# ASD2113.net
KiCad netlist of a schematic drawn in EAGLE
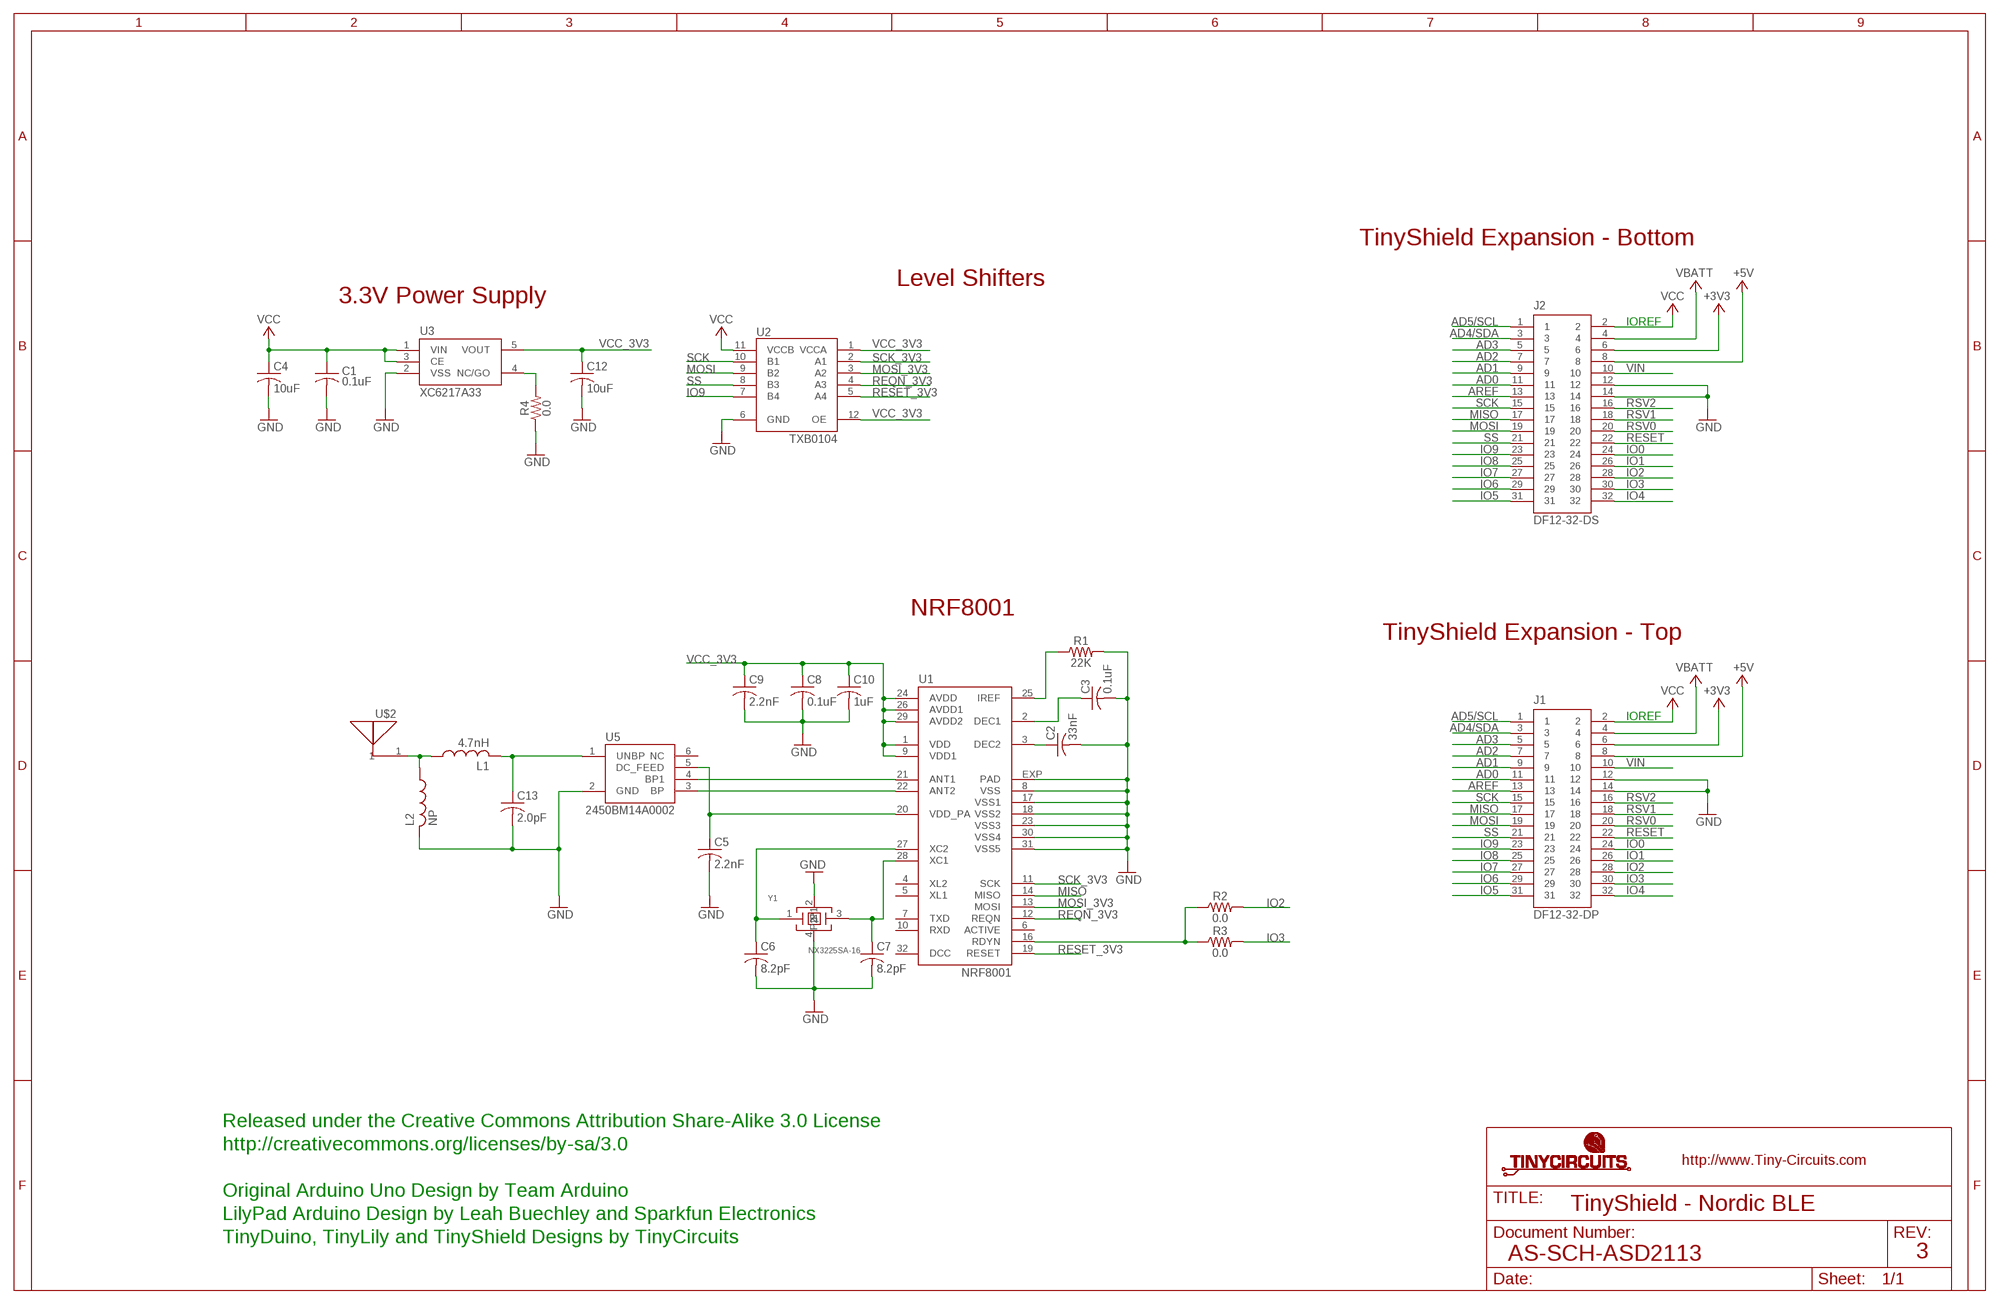
[diagram p0: schematic, sheet 1]

(export (version "E")
  (design (tool "Eeschema 10.0.6"))
  (components
    (comp (ref "C1")
      (value "0.1uF")
      (footprint "eagle-import:C0402")
      (fields (field (name "PARTNO") "AS-ITM-00008") (field (name "PARTNO_1") "AS-ITM-00008"))
      (libsource (lib "eagle-import") (part "AS-ITM-00008"))
    )
    (comp (ref "C2")
      (value "33nF")
      (footprint "eagle-import:C0402")
      (fields (field (name "PARTNO") "AS-ITM-00248") (field (name "PARTNO_1") "AS-ITM-00248"))
      (libsource (lib "eagle-import") (part "AS-ITM-00248"))
    )
    (comp (ref "C3")
      (value "0.1uF")
      (footprint "eagle-import:C0402")
      (fields (field (name "PARTNO") "AS-ITM-00008"))
      (libsource (lib "eagle-import") (part "AS-ITM-00008"))
    )
    (comp (ref "C4")
      (value "10uF")
      (footprint "eagle-import:C0805")
      (fields (field (name "PARTNO") "AS-ITM-00045") (field (name "PARTNO_1") "AS-ITM-00045"))
      (libsource (lib "eagle-import") (part "AS-ITM-00045"))
    )
    (comp (ref "C5")
      (value "2.2nF")
      (footprint "eagle-import:C0402")
      (fields (field (name "PARTNO") "AS-ITM-00085"))
      (libsource (lib "eagle-import") (part "AS-ITM-00085"))
    )
    (comp (ref "C6")
      (value "8.2pF")
      (footprint "eagle-import:C0402")
      (fields (field (name "PARTNO") "AS-ITM-00247") (field (name "PARTNO_1") "AS-ITM-00247"))
      (libsource (lib "eagle-import") (part "AS-ITM-00247"))
    )
    (comp (ref "C7")
      (value "8.2pF")
      (footprint "eagle-import:C0402")
      (fields (field (name "PARTNO") "AS-ITM-00247") (field (name "PARTNO_1") "AS-ITM-00247"))
      (libsource (lib "eagle-import") (part "AS-ITM-00247"))
    )
    (comp (ref "C8")
      (value "0.1uF")
      (footprint "eagle-import:C0402")
      (fields (field (name "PARTNO") "AS-ITM-00008"))
      (libsource (lib "eagle-import") (part "AS-ITM-00008"))
    )
    (comp (ref "C9")
      (value "2.2nF")
      (footprint "eagle-import:C0402")
      (fields (field (name "PARTNO") "AS-ITM-00085"))
      (libsource (lib "eagle-import") (part "AS-ITM-00085"))
    )
    (comp (ref "C10")
      (value "1uF")
      (footprint "eagle-import:C0402")
      (fields (field (name "PARTNO") "AS-ITM-00105"))
      (libsource (lib "eagle-import") (part "AS-ITM-00105"))
    )
    (comp (ref "C12")
      (value "10uF")
      (footprint "eagle-import:C0805")
      (fields (field (name "PARTNO") "AS-ITM-00045") (field (name "PARTNO_1") "AS-ITM-00045"))
      (libsource (lib "eagle-import") (part "AS-ITM-00045"))
    )
    (comp (ref "C13")
      (value "2.0pF")
      (footprint "eagle-import:C0402")
      (fields (field (name "PARTNO") "AS-ITM-00245") (field (name "PARTNO_1") "AS-ITM-00245"))
      (libsource (lib "eagle-import") (part "AS-ITM-00245"))
    )
    (comp (ref "J1")
      (value "DF12-32-DP")
      (footprint "eagle-import:DF12-32-DP")
      (fields (field (name "PARTNO") "AS-ITM-00015") (field (name "PARTNO_1") "AS-ITM-00015"))
      (libsource (lib "eagle-import") (part "AS-ITM-00015"))
    )
    (comp (ref "J2")
      (value "DF12-32-DS")
      (footprint "eagle-import:DF12-32-DS")
      (fields (field (name "PARTNO") "AS-ITM-00012") (field (name "PARTNO_1") "AS-ITM-00012"))
      (libsource (lib "eagle-import") (part "AS-ITM-00012"))
    )
    (comp (ref "L1")
      (value "4.7nH")
      (footprint "eagle-import:C0402")
      (fields (field (name "PARTNO") "AS-ITM-00246") (field (name "PARTNO_1") "AS-ITM-00246"))
      (libsource (lib "eagle-import") (part "AS-ITM-00246"))
    )
    (comp (ref "L2")
      (value "NP")
      (footprint "eagle-import:C0402")
      (fields (field (name "PARTNO") "AS-ITM-00108"))
      (libsource (lib "eagle-import") (part "AS-ITM-00108"))
    )
    (comp (ref "R1")
      (value "22K")
      (footprint "eagle-import:0402")
      (fields (field (name "PARTNO") "AS-ITM-00147"))
      (libsource (lib "eagle-import") (part "AS-ITM-00147"))
    )
    (comp (ref "R2")
      (value "0.0")
      (footprint "eagle-import:0402")
      (fields (field (name "PARTNO") "AS-ITM-00076") (field (name "PARTNO_1") "AS-ITM-00076"))
      (libsource (lib "eagle-import") (part "AS-ITM-00076"))
    )
    (comp (ref "R3")
      (value "0.0")
      (footprint "eagle-import:0402")
      (fields (field (name "PARTNO") "AS-ITM-00076") (field (name "PARTNO_1") "AS-ITM-00076"))
      (libsource (lib "eagle-import") (part "AS-ITM-00076"))
    )
    (comp (ref "R4")
      (value "0.0")
      (footprint "eagle-import:0402")
      (fields (field (name "PARTNO") "AS-ITM-00076"))
      (libsource (lib "eagle-import") (part "AS-ITM-00076"))
    )
    (comp (ref "U$2")
      (value "AS-ITM-00132")
      (footprint "eagle-import:2450AT18A100")
      (fields (field (name "PARTNO") "AS-ITM-00132"))
      (libsource (lib "eagle-import") (part "AS-ITM-00132"))
    )
    (comp (ref "U1")
      (value "NRF8001")
      (footprint "eagle-import:ATMEL_QFN32")
      (fields (field (name "PARTNO") "AS-ITM-00227"))
      (libsource (lib "eagle-import") (part "AS-ITM-00227"))
    )
    (comp (ref "U2")
      (value "TXB0104")
      (footprint "eagle-import:UQFN-12")
      (fields (field (name "PARTNO") "AS-ITM-00048"))
      (libsource (lib "eagle-import") (part "AS-ITM-00048"))
    )
    (comp (ref "U3")
      (value "XC6217A33")
      (footprint "eagle-import:SOT-25")
      (fields (field (name "PARTNO") "AS-ITM-00249") (field (name "PARTNO_1") "AS-ITM-00249"))
      (libsource (lib "eagle-import") (part "AS-ITM-00249"))
    )
    (comp (ref "U5")
      (value "2450BM14A0002")
      (footprint "eagle-import:2450BM14A0002")
      (fields (field (name "PARTNO") "AS-ITM-00114"))
      (libsource (lib "eagle-import") (part "AS-ITM-00114"))
    )
    (comp (ref "Y1")
      (value "NX3225SA-16")
      (footprint "eagle-import:ABM11")
      (fields (field (name "PARTNO") "AS-ITM-00228") (field (name "PARTNO_1") "AS-ITM-00228"))
      (libsource (lib "eagle-import") (part "AS-ITM-00228"))
    )
  )
  (nets
    (net (code "1") (name "+3V3") (class "Default")
      (node (ref "J1") (pin "6") (pinfunction "6_6") (pintype "bidirectional"))
      (node (ref "J2") (pin "6") (pinfunction "6_6") (pintype "bidirectional"))
    )
    (net (code "2") (name "+5V") (class "Default")
      (node (ref "J1") (pin "8") (pinfunction "8_8") (pintype "bidirectional"))
      (node (ref "J2") (pin "8") (pinfunction "8_8") (pintype "bidirectional"))
    )
    (net (code "3") (name "/AD0") (class "Default")
      (node (ref "J1") (pin "11") (pinfunction "11_11") (pintype "bidirectional"))
      (node (ref "J2") (pin "11") (pinfunction "11_11") (pintype "bidirectional"))
    )
    (net (code "4") (name "/AD1") (class "Default")
      (node (ref "J1") (pin "9") (pinfunction "9_9") (pintype "bidirectional"))
      (node (ref "J2") (pin "9") (pinfunction "9_9") (pintype "bidirectional"))
    )
    (net (code "5") (name "/AD2") (class "Default")
      (node (ref "J1") (pin "7") (pinfunction "7_7") (pintype "bidirectional"))
      (node (ref "J2") (pin "7") (pinfunction "7_7") (pintype "bidirectional"))
    )
    (net (code "6") (name "/AD3") (class "Default")
      (node (ref "J1") (pin "5") (pinfunction "5_5") (pintype "bidirectional"))
      (node (ref "J2") (pin "5") (pinfunction "5_5") (pintype "bidirectional"))
    )
    (net (code "7") (name "/AD4{slash}SDA") (class "Default")
      (node (ref "J1") (pin "3") (pinfunction "3_3") (pintype "bidirectional"))
      (node (ref "J2") (pin "3") (pinfunction "3_3") (pintype "bidirectional"))
    )
    (net (code "8") (name "/AD5{slash}SCL") (class "Default")
      (node (ref "J1") (pin "1") (pinfunction "1_1") (pintype "bidirectional"))
      (node (ref "J2") (pin "1") (pinfunction "1_1") (pintype "bidirectional"))
    )
    (net (code "9") (name "/AREF") (class "Default")
      (node (ref "J1") (pin "13") (pinfunction "13_13") (pintype "bidirectional"))
      (node (ref "J2") (pin "13") (pinfunction "13_13") (pintype "bidirectional"))
    )
    (net (code "10") (name "/IO0") (class "Default")
      (node (ref "J1") (pin "24") (pinfunction "24_24") (pintype "bidirectional"))
      (node (ref "J2") (pin "24") (pinfunction "24_24") (pintype "bidirectional"))
    )
    (net (code "11") (name "/IO1") (class "Default")
      (node (ref "J1") (pin "26") (pinfunction "26_26") (pintype "bidirectional"))
      (node (ref "J2") (pin "26") (pinfunction "26_26") (pintype "bidirectional"))
    )
    (net (code "12") (name "/IO2") (class "Default")
      (node (ref "J1") (pin "28") (pinfunction "28_28") (pintype "bidirectional"))
      (node (ref "J2") (pin "28") (pinfunction "28_28") (pintype "bidirectional"))
      (node (ref "R2") (pin "2") (pinfunction "2_2") (pintype "passive"))
    )
    (net (code "13") (name "/IO3") (class "Default")
      (node (ref "J1") (pin "30") (pinfunction "30_30") (pintype "bidirectional"))
      (node (ref "J2") (pin "30") (pinfunction "30_30") (pintype "bidirectional"))
      (node (ref "R3") (pin "2") (pinfunction "2_2") (pintype "passive"))
    )
    (net (code "14") (name "/IO4") (class "Default")
      (node (ref "J1") (pin "32") (pinfunction "32_32") (pintype "bidirectional"))
      (node (ref "J2") (pin "32") (pinfunction "32_32") (pintype "bidirectional"))
    )
    (net (code "15") (name "/IO5") (class "Default")
      (node (ref "J1") (pin "31") (pinfunction "31_31") (pintype "bidirectional"))
      (node (ref "J2") (pin "31") (pinfunction "31_31") (pintype "bidirectional"))
    )
    (net (code "16") (name "/IO6") (class "Default")
      (node (ref "J1") (pin "29") (pinfunction "29_29") (pintype "bidirectional"))
      (node (ref "J2") (pin "29") (pinfunction "29_29") (pintype "bidirectional"))
    )
    (net (code "17") (name "/IO7") (class "Default")
      (node (ref "J1") (pin "27") (pinfunction "27_27") (pintype "bidirectional"))
      (node (ref "J2") (pin "27") (pinfunction "27_27") (pintype "bidirectional"))
    )
    (net (code "18") (name "/IO8") (class "Default")
      (node (ref "J1") (pin "25") (pinfunction "25_25") (pintype "bidirectional"))
      (node (ref "J2") (pin "25") (pinfunction "25_25") (pintype "bidirectional"))
    )
    (net (code "19") (name "/IO9") (class "Default")
      (node (ref "J1") (pin "23") (pinfunction "23_23") (pintype "bidirectional"))
      (node (ref "J2") (pin "23") (pinfunction "23_23") (pintype "bidirectional"))
      (node (ref "U2") (pin "7") (pinfunction "B4_7") (pintype "bidirectional"))
    )
    (net (code "20") (name "/MISO") (class "Default")
      (node (ref "J1") (pin "17") (pinfunction "17_17") (pintype "bidirectional"))
      (node (ref "J2") (pin "17") (pinfunction "17_17") (pintype "bidirectional"))
      (node (ref "U1") (pin "14") (pinfunction "MISO_14") (pintype "bidirectional"))
    )
    (net (code "21") (name "/MOSI") (class "Default")
      (node (ref "J1") (pin "19") (pinfunction "19_19") (pintype "bidirectional"))
      (node (ref "J2") (pin "19") (pinfunction "19_19") (pintype "bidirectional"))
      (node (ref "U2") (pin "9") (pinfunction "B2_9") (pintype "bidirectional"))
    )
    (net (code "22") (name "/MOSI_3V3") (class "Default")
      (node (ref "U1") (pin "13") (pinfunction "MOSI_13") (pintype "bidirectional"))
      (node (ref "U2") (pin "3") (pinfunction "A2_3") (pintype "bidirectional"))
    )
    (net (code "23") (name "/REQN_3V3") (class "Default")
      (node (ref "U1") (pin "12") (pinfunction "REQN_12") (pintype "bidirectional"))
      (node (ref "U2") (pin "4") (pinfunction "A3_4") (pintype "bidirectional"))
    )
    (net (code "24") (name "/RESET") (class "Default")
      (node (ref "J1") (pin "22") (pinfunction "22_22") (pintype "bidirectional"))
      (node (ref "J2") (pin "22") (pinfunction "22_22") (pintype "bidirectional"))
    )
    (net (code "25") (name "/RESET_3V3") (class "Default")
      (node (ref "U1") (pin "19") (pinfunction "RESET_19") (pintype "bidirectional"))
      (node (ref "U2") (pin "5") (pinfunction "A4_5") (pintype "bidirectional"))
    )
    (net (code "26") (name "/RSV0") (class "Default")
      (node (ref "J1") (pin "20") (pinfunction "20_20") (pintype "bidirectional"))
      (node (ref "J2") (pin "20") (pinfunction "20_20") (pintype "bidirectional"))
    )
    (net (code "27") (name "/RSV1") (class "Default")
      (node (ref "J1") (pin "18") (pinfunction "18_18") (pintype "bidirectional"))
      (node (ref "J2") (pin "18") (pinfunction "18_18") (pintype "bidirectional"))
    )
    (net (code "28") (name "/RSV2") (class "Default")
      (node (ref "J1") (pin "16") (pinfunction "16_16") (pintype "bidirectional"))
      (node (ref "J2") (pin "16") (pinfunction "16_16") (pintype "bidirectional"))
    )
    (net (code "29") (name "/SCK") (class "Default")
      (node (ref "J1") (pin "15") (pinfunction "15_15") (pintype "bidirectional"))
      (node (ref "J2") (pin "15") (pinfunction "15_15") (pintype "bidirectional"))
      (node (ref "U2") (pin "10") (pinfunction "B1_10") (pintype "bidirectional"))
    )
    (net (code "30") (name "/SCK_3V3") (class "Default")
      (node (ref "U1") (pin "11") (pinfunction "SCK_11") (pintype "bidirectional"))
      (node (ref "U2") (pin "2") (pinfunction "A1_2") (pintype "bidirectional"))
    )
    (net (code "31") (name "/SS") (class "Default")
      (node (ref "J1") (pin "21") (pinfunction "21_21") (pintype "bidirectional"))
      (node (ref "J2") (pin "21") (pinfunction "21_21") (pintype "bidirectional"))
      (node (ref "U2") (pin "8") (pinfunction "B3_8") (pintype "bidirectional"))
    )
    (net (code "32") (name "/VCC_3V3") (class "Default")
      (node (ref "C10") (pin "1") (pinfunction "1_1") (pintype "passive"))
      (node (ref "C12") (pin "1") (pinfunction "1_1") (pintype "passive"))
      (node (ref "C8") (pin "1") (pinfunction "1_1") (pintype "passive"))
      (node (ref "C9") (pin "1") (pinfunction "1_1") (pintype "passive"))
      (node (ref "U1") (pin "1") (pinfunction "VDD_1") (pintype "bidirectional"))
      (node (ref "U1") (pin "24") (pinfunction "AVDD_24") (pintype "bidirectional"))
      (node (ref "U1") (pin "26") (pinfunction "AVDD1_26") (pintype "bidirectional"))
      (node (ref "U1") (pin "29") (pinfunction "AVDD2_29") (pintype "bidirectional"))
      (node (ref "U1") (pin "9") (pinfunction "VDD1_9") (pintype "bidirectional"))
      (node (ref "U2") (pin "1") (pinfunction "VCCA_1") (pintype "bidirectional"))
      (node (ref "U2") (pin "12") (pinfunction "OE_12") (pintype "bidirectional"))
      (node (ref "U3") (pin "5") (pinfunction "VOUT_5") (pintype "bidirectional"))
    )
    (net (code "33") (name "/VIN") (class "Default")
      (node (ref "J1") (pin "10") (pinfunction "10_10") (pintype "bidirectional"))
      (node (ref "J2") (pin "10") (pinfunction "10_10") (pintype "bidirectional"))
    )
    (net (code "34") (name "GND") (class "Default")
      (node (ref "C1") (pin "2") (pinfunction "2_2") (pintype "passive"))
      (node (ref "C10") (pin "2") (pinfunction "2_2") (pintype "passive"))
      (node (ref "C12") (pin "2") (pinfunction "2_2") (pintype "passive"))
      (node (ref "C13") (pin "2") (pinfunction "2_2") (pintype "passive"))
      (node (ref "C2") (pin "2") (pinfunction "2_2") (pintype "passive"))
      (node (ref "C3") (pin "2") (pinfunction "2_2") (pintype "passive"))
      (node (ref "C4") (pin "2") (pinfunction "2_2") (pintype "passive"))
      (node (ref "C5") (pin "2") (pinfunction "2_2") (pintype "passive"))
      (node (ref "C6") (pin "2") (pinfunction "2_2") (pintype "passive"))
      (node (ref "C7") (pin "2") (pinfunction "2_2") (pintype "passive"))
      (node (ref "C8") (pin "2") (pinfunction "2_2") (pintype "passive"))
      (node (ref "C9") (pin "2") (pinfunction "2_2") (pintype "passive"))
      (node (ref "J1") (pin "12") (pinfunction "12_12") (pintype "bidirectional"))
      (node (ref "J1") (pin "14") (pinfunction "14_14") (pintype "bidirectional"))
      (node (ref "J2") (pin "12") (pinfunction "12_12") (pintype "bidirectional"))
      (node (ref "J2") (pin "14") (pinfunction "14_14") (pintype "bidirectional"))
      (node (ref "L2") (pin "2") (pinfunction "2_2") (pintype "passive"))
      (node (ref "R1") (pin "2") (pinfunction "2_2") (pintype "passive"))
      (node (ref "R4") (pin "1") (pinfunction "1_1") (pintype "passive"))
      (node (ref "U1") (pin "17") (pinfunction "VSS1_17") (pintype "bidirectional"))
      (node (ref "U1") (pin "18") (pinfunction "VSS2_18") (pintype "bidirectional"))
      (node (ref "U1") (pin "23") (pinfunction "VSS3_23") (pintype "bidirectional"))
      (node (ref "U1") (pin "30") (pinfunction "VSS4_30") (pintype "bidirectional"))
      (node (ref "U1") (pin "31") (pinfunction "VSS5_31") (pintype "bidirectional"))
      (node (ref "U1") (pin "8") (pinfunction "VSS_8") (pintype "bidirectional"))
      (node (ref "U1") (pin "EXP") (pinfunction "PAD_EXP") (pintype "bidirectional"))
      (node (ref "U2") (pin "6") (pinfunction "GND_6") (pintype "bidirectional"))
      (node (ref "U3") (pin "2") (pinfunction "VSS_2") (pintype "power_in"))
      (node (ref "U5") (pin "2") (pinfunction "GND_2") (pintype "bidirectional"))
      (node (ref "Y1") (pin "2") (pinfunction "P2_2") (pintype "bidirectional"))
      (node (ref "Y1") (pin "4") (pinfunction "P1_4") (pintype "bidirectional"))
    )
    (net (code "35") (name "Net-(L1-Pad1)") (class "Default")
      (node (ref "L1") (pin "1") (pinfunction "1_1") (pintype "passive"))
      (node (ref "L2") (pin "1") (pinfunction "1_1") (pintype "passive"))
      (node (ref "U$2") (pin "1") (pinfunction "1_1") (pintype "bidirectional"))
    )
    (net (code "36") (name "Net-(U1-ANT1)") (class "Default")
      (node (ref "U1") (pin "21") (pinfunction "ANT1_21") (pintype "bidirectional"))
      (node (ref "U5") (pin "4") (pinfunction "BP1_4") (pintype "bidirectional"))
    )
    (net (code "37") (name "Net-(U1-ANT2)") (class "Default")
      (node (ref "U1") (pin "22") (pinfunction "ANT2_22") (pintype "bidirectional"))
      (node (ref "U5") (pin "3") (pinfunction "BP_3") (pintype "bidirectional"))
    )
    (net (code "38") (name "Net-(U1-DEC1)") (class "Default")
      (node (ref "C3") (pin "1") (pinfunction "1_1") (pintype "passive"))
      (node (ref "U1") (pin "2") (pinfunction "DEC1_2") (pintype "bidirectional"))
    )
    (net (code "39") (name "Net-(U1-DEC2)") (class "Default")
      (node (ref "C2") (pin "1") (pinfunction "1_1") (pintype "passive"))
      (node (ref "U1") (pin "3") (pinfunction "DEC2_3") (pintype "bidirectional"))
    )
    (net (code "40") (name "Net-(U1-IREF)") (class "Default")
      (node (ref "R1") (pin "1") (pinfunction "1_1") (pintype "passive"))
      (node (ref "U1") (pin "25") (pinfunction "IREF_25") (pintype "bidirectional"))
    )
    (net (code "41") (name "Net-(U1-RDYN)") (class "Default")
      (node (ref "R2") (pin "1") (pinfunction "1_1") (pintype "passive"))
      (node (ref "R3") (pin "1") (pinfunction "1_1") (pintype "passive"))
      (node (ref "U1") (pin "16") (pinfunction "RDYN_16") (pintype "bidirectional"))
    )
    (net (code "42") (name "Net-(U1-VDD_PA)") (class "Default")
      (node (ref "C5") (pin "1") (pinfunction "1_1") (pintype "passive"))
      (node (ref "U1") (pin "20") (pinfunction "VDD_PA_20") (pintype "bidirectional"))
      (node (ref "U5") (pin "5") (pinfunction "DC_FEED_5") (pintype "bidirectional"))
    )
    (net (code "43") (name "Net-(U1-XC1)") (class "Default")
      (node (ref "C7") (pin "1") (pinfunction "1_1") (pintype "passive"))
      (node (ref "U1") (pin "28") (pinfunction "XC1_28") (pintype "bidirectional"))
      (node (ref "Y1") (pin "3") (pinfunction "2_3") (pintype "bidirectional"))
    )
    (net (code "44") (name "Net-(U1-XC2)") (class "Default")
      (node (ref "C6") (pin "1") (pinfunction "1_1") (pintype "passive"))
      (node (ref "U1") (pin "27") (pinfunction "XC2_27") (pintype "bidirectional"))
      (node (ref "Y1") (pin "1") (pinfunction "1_1") (pintype "bidirectional"))
    )
    (net (code "45") (name "Net-(U3-NC{slash}GO)") (class "Default")
      (node (ref "R4") (pin "2") (pinfunction "2_2") (pintype "passive"))
      (node (ref "U3") (pin "4") (pinfunction "NC/GO_4") (pintype "bidirectional"))
    )
    (net (code "46") (name "Net-(U5-UNBP)") (class "Default")
      (node (ref "C13") (pin "1") (pinfunction "1_1") (pintype "passive"))
      (node (ref "L1") (pin "2") (pinfunction "2_2") (pintype "passive"))
      (node (ref "U5") (pin "1") (pinfunction "UNBP_1") (pintype "bidirectional"))
    )
    (net (code "47") (name "VBATT") (class "Default")
      (node (ref "J1") (pin "4") (pinfunction "4_4") (pintype "bidirectional"))
      (node (ref "J2") (pin "4") (pinfunction "4_4") (pintype "bidirectional"))
    )
    (net (code "48") (name "VCC") (class "Default")
      (node (ref "C1") (pin "1") (pinfunction "1_1") (pintype "passive"))
      (node (ref "C4") (pin "1") (pinfunction "1_1") (pintype "passive"))
      (node (ref "J1") (pin "2") (pinfunction "2_2") (pintype "bidirectional"))
      (node (ref "J2") (pin "2") (pinfunction "2_2") (pintype "bidirectional"))
      (node (ref "U2") (pin "11") (pinfunction "VCCB_11") (pintype "bidirectional"))
      (node (ref "U3") (pin "1") (pinfunction "VIN_1") (pintype "bidirectional"))
      (node (ref "U3") (pin "3") (pinfunction "CE_3") (pintype "bidirectional"))
    )
    (net (code "49") (name "unconnected-(U$2-Pad2)") (class "Default")
      (node (ref "U$2") (pin "2") (pinfunction "2_2") (pintype "bidirectional"))
    )
    (net (code "50") (name "unconnected-(U1-ACTIVE-Pad6)") (class "Default")
      (node (ref "U1") (pin "6") (pinfunction "ACTIVE_6") (pintype "bidirectional"))
    )
    (net (code "51") (name "unconnected-(U1-DCC-Pad32)") (class "Default")
      (node (ref "U1") (pin "32") (pinfunction "DCC_32") (pintype "bidirectional"))
    )
    (net (code "52") (name "unconnected-(U1-RXD-Pad10)") (class "Default")
      (node (ref "U1") (pin "10") (pinfunction "RXD_10") (pintype "bidirectional"))
    )
    (net (code "53") (name "unconnected-(U1-TXD-Pad7)") (class "Default")
      (node (ref "U1") (pin "7") (pinfunction "TXD_7") (pintype "bidirectional"))
    )
    (net (code "54") (name "unconnected-(U1-XL1-Pad5)") (class "Default")
      (node (ref "U1") (pin "5") (pinfunction "XL1_5") (pintype "bidirectional"))
    )
    (net (code "55") (name "unconnected-(U1-XL2-Pad4)") (class "Default")
      (node (ref "U1") (pin "4") (pinfunction "XL2_4") (pintype "bidirectional"))
    )
    (net (code "56") (name "unconnected-(U5-NC-Pad6)") (class "Default")
      (node (ref "U5") (pin "6") (pinfunction "NC_6") (pintype "bidirectional"))
    )
  )
)
